# yard-ice-toplevel.net
KiCad netlist of a schematic drawn in Altium Designer
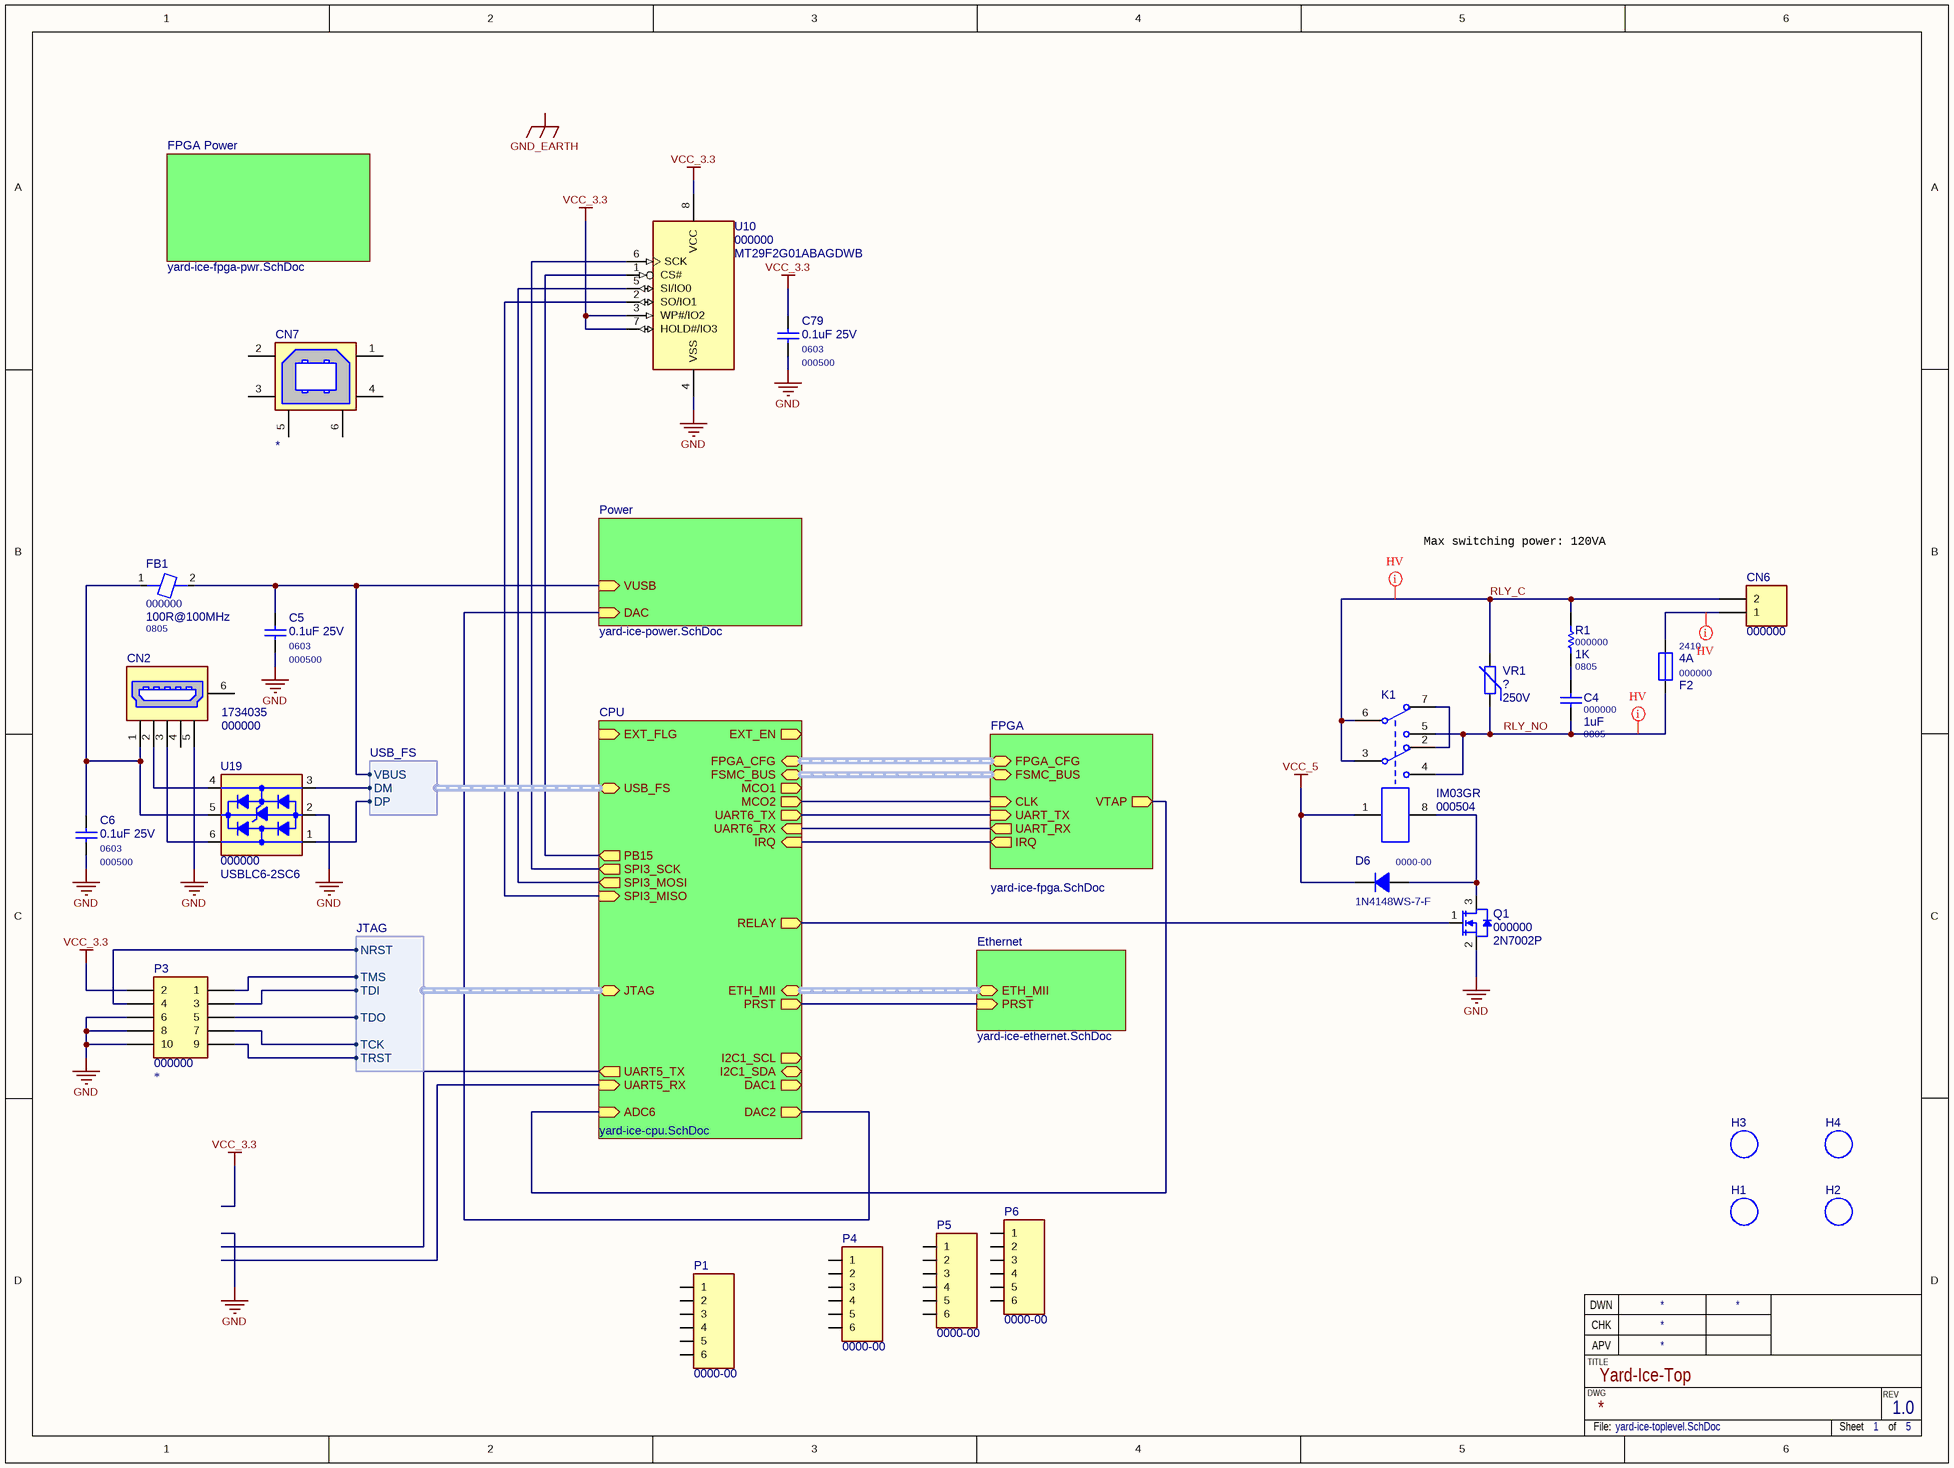
[diagram p0: yard-ice-toplevel.SchDoc]

(export (version "E")
  (design (tool "Eeschema 10.0.6"))
  (components
    (comp (ref "C4")
      (value "000000")
      (footprint "C0805HV")
      (description "SMD Ceramic Chip Capacitor - 0805")
      (fields (field (name "ALTIUM_VALUE") "1uF") (field (name "PACKAGE") "0805"))
      (libsource (lib "discrete-sm") (part "C0805"))
    )
    (comp (ref "C5")
      (value "000500")
      (footprint "C0603M")
      (description "SMD Ceramic Chip Capacitor - 0603 - X7R")
      (fields
        (field (name "ALTIUM_VALUE") "0.1uF 25V")
        (field (name "PACKAGE") "0603")
        (field (name "MF") "TDK")
      )
      (libsource (lib "discrete-sm") (part "C0603"))
    )
    (comp (ref "C6")
      (value "000500")
      (footprint "C0603M")
      (description "SMD Ceramic Chip Capacitor - 0603 - X7R")
      (fields
        (field (name "ALTIUM_VALUE") "0.1uF 25V")
        (field (name "PACKAGE") "0603")
        (field (name "MF") "TDK")
      )
      (libsource (lib "discrete-sm") (part "C0603"))
    )
    (comp (ref "C79")
      (value "000500")
      (footprint "C0603M")
      (description "SMD Ceramic Chip Capacitor - 0603 - X7R")
      (fields
        (field (name "ALTIUM_VALUE") "0.1uF 25V")
        (field (name "PACKAGE") "0603")
        (field (name "MF") "TDK")
      )
      (libsource (lib "discrete-sm") (part "C0603"))
    )
    (comp (ref "CN2")
      (value "1734035")
      (footprint "1734035")
      (description "USB Type B Mini - Right Angle - SMD")
      (fields (field (name "MF") "Tyco") (field (name "PN") "000000") (field (name "Comment") "000000"))
      (libsource (lib "tyco-conn") (part "1734035"))
    )
    (comp (ref "CN6")
      (value "000000")
      (footprint "691322110002")
      (description "Terminal Block, Header, 2-Pos")
      (libsource (lib "wurth") (part "Term Blk 2"))
    )
    (comp (ref "CN7")
      (value "*")
      (footprint "4-1734376")
      (description "USB Type B - Right Angle - Thru Hole")
      (libsource (lib "tyco-conn") (part "4-1734376"))
    )
    (comp (ref "D6")
      (value "0000-00")
      (footprint "SOD-323-M")
      (description "Fast Switching Diode 100V 150mA")
      (fields (field (name "MF") "Diodes Inc") (field (name "MF PN") "1N4148WS-7-F"))
      (libsource (lib "diodes-inc") (part "1N4148WS"))
    )
    (comp (ref "F2")
      (value "000000")
      (footprint "F2410")
      (fields (field (name "PACKAGE") "2410") (field (name "ALTIUM_VALUE") "4A"))
      (libsource (lib "discrete-sm") (part "F2410"))
    )
    (comp (ref "FB1")
      (value "000000")
      (footprint "L0805M")
      (description "SMD Chip Ferrite Bead - 0805")
      (fields (field (name "ALTIUM_VALUE") "100R@100MHz") (field (name "PACKAGE") "0805"))
      (libsource (lib "discrete-sm") (part "FB0805"))
    )
    (comp (ref "H1")
      (value "Hole Non Plated")
      (footprint "Hole NP 3.2x5.0x5.0")
      (libsource (lib "mechanical") (part "Hole Non Plated"))
    )
    (comp (ref "H2")
      (value "Hole Non Plated")
      (footprint "Hole NP 3.2x5.0x5.0")
      (libsource (lib "mechanical") (part "Hole Non Plated"))
    )
    (comp (ref "H3")
      (value "Hole Non Plated")
      (footprint "Hole NP 3.2x5.0x5.0")
      (libsource (lib "mechanical") (part "Hole Non Plated"))
    )
    (comp (ref "H4")
      (value "Hole Non Plated")
      (footprint "Hole NP 3.2x5.0x5.0")
      (libsource (lib "mechanical") (part "Hole Non Plated"))
    )
    (comp (ref "K1")
      (value "000504")
      (footprint "Relay-10X6")
      (description "Dual-Pole Dual-Throw Relay")
      (fields (field (name "ALTIUM_VALUE") "IM03GR") (field (name "MF") "Tyco"))
      (libsource (lib "sm-electromechanical") (part "Relay-DPDT"))
    )
    (comp (ref "P1")
      (value "0000-00")
      (footprint "SsW-106-01-G-S")
      (description "Header, 6-Pin")
      (fields (field (name "MF") "Samtec"))
      (libsource (lib "samtec-board-to-board") (part "Header 6"))
    )
    (comp (ref "P3")
      (value "000000")
      (footprint "TSW-105-07-G-D")
      (description "Socket 5-Pin, Dual row")
      (fields (field (name "ALTIUM_VALUE") "*"))
      (libsource (lib "samtec-std-hdr") (part "Header 5X2"))
    )
    (comp (ref "P4")
      (value "0000-00")
      (footprint "SsW-106-01-G-S")
      (description "Header, 6-Pin")
      (fields (field (name "MF") "Samtec"))
      (libsource (lib "samtec-board-to-board") (part "Header 6"))
    )
    (comp (ref "P5")
      (value "0000-00")
      (footprint "SsW-106-01-G-S")
      (description "Header, 6-Pin")
      (fields (field (name "MF") "Samtec"))
      (libsource (lib "samtec-board-to-board") (part "Header 6"))
    )
    (comp (ref "P6")
      (value "0000-00")
      (footprint "SsW-106-01-G-S")
      (description "Header, 6-Pin")
      (fields (field (name "MF") "Samtec"))
      (libsource (lib "samtec-board-to-board") (part "Header 6"))
    )
    (comp (ref "Q1")
      (value "000000")
      (footprint "SOT-23-M")
      (description "N-Channel MOSFET 60V 360mA SOT-23")
      (fields (field (name "ALTIUM_VALUE") "2N7002P"))
      (libsource (lib "nxp") (part "2N7002P"))
    )
    (comp (ref "R1")
      (value "000000")
      (footprint "R0805HV")
      (description "SMD Chip Resistor - 0805")
      (fields (field (name "ALTIUM_VALUE") "1K") (field (name "PACKAGE") "0805"))
      (libsource (lib "discrete-sm") (part "R0805"))
    )
    (comp (ref "U10")
      (value "000000")
      (footprint "U-PDFN-8")
      (description "2Gb NANDl Flash Memory,  133MHz, SPI")
      (fields (field (name "MF") "Micron") (field (name "ALTIUM_VALUE") "MT29F2G01ABAGDWB"))
      (libsource (lib "micron") (part "MT29F2G01ABAGDWB"))
    )
    (comp (ref "U19")
      (value "000000")
      (footprint "SOT23-6L")
      (description "USB ESD Protection")
      (fields (field (name "MF") "STMicroelectronics") (field (name "ALTIUM_VALUE") "USBLC6-2SC6"))
      (libsource (lib "st") (part "USBLC6-2SC6"))
    )
    (comp (ref "VR1")
      (value "?")
      (footprint "MOV7x4.8-5.0")
      (description "Varistor (Voltage-Sensitive Resistor)")
      (fields (field (name "ALTIUM_VALUE") "250V"))
      (libsource (lib "discrete-pth") (part "Varistor"))
    )
  )
  (nets
    (net (code "15") (name "/PB15") (class "Default")
      (node (ref "U10") (pin "1") (pinfunction "CS#_1") (pintype "input"))
    )
    (net (code "17") (name "/RELAY") (class "Default")
      (node (ref "Q1") (pin "1") (pinfunction "G_1") (pintype "passive"))
    )
    (net (code "18") (name "/RLY_C") (class "Default")
      (node (ref "CN6") (pin "2") (pinfunction "2_2") (pintype "passive"))
      (node (ref "K1") (pin "3") (pinfunction "3_3") (pintype "passive"))
      (node (ref "K1") (pin "6") (pinfunction "6_6") (pintype "passive"))
      (node (ref "R1") (pin "2") (pinfunction "2_2") (pintype "passive"))
      (node (ref "VR1") (pin "2") (pinfunction "2_2") (pintype "passive"))
    )
    (net (code "19") (name "/RLY_NO") (class "Default")
      (node (ref "C4") (pin "2") (pinfunction "2_2") (pintype "passive"))
      (node (ref "F2") (pin "1") (pinfunction "1_1") (pintype "passive"))
      (node (ref "K1") (pin "4") (pinfunction "4_4") (pintype "passive"))
      (node (ref "K1") (pin "5") (pinfunction "5_5") (pintype "passive"))
      (node (ref "VR1") (pin "1") (pinfunction "1_1") (pintype "passive"))
    )
    (net (code "20") (name "/SPI3_MISO") (class "Default")
      (node (ref "U10") (pin "2") (pinfunction "SO/IO1_2") (pintype "bidirectional"))
    )
    (net (code "21") (name "/SPI3_MOSI") (class "Default")
      (node (ref "U10") (pin "5") (pinfunction "SI/IO0_5") (pintype "bidirectional"))
    )
    (net (code "22") (name "/SPI3_SCK") (class "Default")
      (node (ref "U10") (pin "6") (pinfunction "SCK_6") (pintype "input"))
    )
    (net (code "28") (name "/VUSB") (class "Default")
      (node (ref "C5") (pin "1") (pinfunction "1_1") (pintype "passive"))
      (node (ref "FB1") (pin "2") (pinfunction "2_2") (pintype "passive"))
    )
    (net (code "31") (name "GND") (class "Default")
      (node (ref "C5") (pin "2") (pinfunction "2_2") (pintype "passive"))
      (node (ref "C6") (pin "2") (pinfunction "2_2") (pintype "passive"))
      (node (ref "C79") (pin "2") (pinfunction "2_2") (pintype "passive"))
      (node (ref "CN2") (pin "5") (pinfunction "SHIELD_5") (pintype "passive"))
      (node (ref "P3") (pin "10") (pinfunction "10_10") (pintype "passive"))
      (node (ref "P3") (pin "6") (pinfunction "6_6") (pintype "passive"))
      (node (ref "P3") (pin "8") (pinfunction "8_8") (pintype "passive"))
      (node (ref "Q1") (pin "2") (pinfunction "S_2") (pintype "passive"))
      (node (ref "U10") (pin "4") (pinfunction "VSS_4") (pintype "power_in"))
      (node (ref "U19") (pin "2") (pinfunction "GND_2") (pintype "power_in"))
    )
    (net (code "33") (name "Net-(C4-Pad1)") (class "Default")
      (node (ref "C4") (pin "1") (pinfunction "1_1") (pintype "passive"))
      (node (ref "R1") (pin "1") (pinfunction "1_1") (pintype "passive"))
    )
    (net (code "34") (name "Net-(CN6-Pad1)") (class "Default")
      (node (ref "CN6") (pin "1") (pinfunction "1_1") (pintype "passive"))
      (node (ref "F2") (pin "2") (pinfunction "2_2") (pintype "passive"))
    )
    (net (code "35") (name "Net-(D6-A)") (class "Default")
      (node (ref "D6") (pin "1") (pinfunction "A_1") (pintype "passive"))
      (node (ref "K1") (pin "8") (pinfunction "8_8") (pintype "passive"))
      (node (ref "Q1") (pin "3") (pinfunction "D_3") (pintype "passive"))
    )
    (net (code "36") (name "Net-(K1-Pad2)") (class "Default")
      (node (ref "K1") (pin "2") (pinfunction "2_2") (pintype "passive"))
      (node (ref "K1") (pin "7") (pinfunction "7_7") (pintype "passive"))
    )
    (net (code "37") (name "Net-(U19-I{slash}O1)") (class "Default")
      (node (ref "CN2") (pin "3") (pinfunction "3_3") (pintype "passive"))
      (node (ref "U19") (pin "6") (pinfunction "I/O1_6") (pintype "open_collector"))
    )
    (net (code "38") (name "Net-(U19-I{slash}O2)") (class "Default")
      (node (ref "CN2") (pin "2") (pinfunction "2_2") (pintype "passive"))
      (node (ref "U19") (pin "4") (pinfunction "I/O2_4") (pintype "open_collector"))
    )
    (net (code "39") (name "Net-(U19-VBUS)") (class "Default")
      (node (ref "C6") (pin "1") (pinfunction "1_1") (pintype "passive"))
      (node (ref "CN2") (pin "1") (pinfunction "1_1") (pintype "passive"))
      (node (ref "FB1") (pin "1") (pinfunction "1_1") (pintype "passive"))
      (node (ref "U19") (pin "5") (pinfunction "VBUS_5") (pintype "power_in"))
    )
    (net (code "40") (name "VCC_3.3") (class "Default")
      (node (ref "C79") (pin "1") (pinfunction "1_1") (pintype "passive"))
      (node (ref "P3") (pin "2") (pinfunction "2_2") (pintype "passive"))
      (node (ref "U10") (pin "3") (pinfunction "WP#/IO2_3") (pintype "input"))
      (node (ref "U10") (pin "7") (pinfunction "HOLD#/IO3_7") (pintype "bidirectional"))
      (node (ref "U10") (pin "8") (pinfunction "VCC_8") (pintype "power_in"))
    )
    (net (code "41") (name "VCC_5") (class "Default")
      (node (ref "D6") (pin "2") (pinfunction "K_2") (pintype "passive"))
      (node (ref "K1") (pin "1") (pinfunction "1_1") (pintype "passive"))
    )
    (net (code "42") (name "unconnected-(CN2-Pad4)") (class "Default")
      (node (ref "CN2") (pin "4") (pinfunction "4_4") (pintype "passive"))
    )
    (net (code "43") (name "unconnected-(CN2-SHIELD-Pad6)") (class "Default")
      (node (ref "CN2") (pin "6") (pinfunction "SHIELD_6") (pintype "passive"))
    )
    (net (code "44") (name "unconnected-(CN7-Pad1)") (class "Default")
      (node (ref "CN7") (pin "1") (pinfunction "1_1") (pintype "passive"))
    )
    (net (code "45") (name "unconnected-(CN7-Pad2)") (class "Default")
      (node (ref "CN7") (pin "2") (pinfunction "2_2") (pintype "passive"))
    )
    (net (code "46") (name "unconnected-(CN7-Pad3)") (class "Default")
      (node (ref "CN7") (pin "3") (pinfunction "3_3") (pintype "passive"))
    )
    (net (code "47") (name "unconnected-(CN7-Pad4)") (class "Default")
      (node (ref "CN7") (pin "4") (pinfunction "4_4") (pintype "passive"))
    )
    (net (code "48") (name "unconnected-(CN7-SHIELD-Pad5)") (class "Default")
      (node (ref "CN7") (pin "5") (pinfunction "SHIELD_5") (pintype "passive"))
    )
    (net (code "49") (name "unconnected-(CN7-SHIELD-Pad6)") (class "Default")
      (node (ref "CN7") (pin "6") (pinfunction "SHIELD_6") (pintype "passive"))
    )
    (net (code "50") (name "unconnected-(P1-Pad1)") (class "Default")
      (node (ref "P1") (pin "1") (pinfunction "1_1") (pintype "passive"))
    )
    (net (code "51") (name "unconnected-(P1-Pad2)") (class "Default")
      (node (ref "P1") (pin "2") (pinfunction "2_2") (pintype "passive"))
    )
    (net (code "52") (name "unconnected-(P1-Pad3)") (class "Default")
      (node (ref "P1") (pin "3") (pinfunction "3_3") (pintype "passive"))
    )
    (net (code "53") (name "unconnected-(P1-Pad4)") (class "Default")
      (node (ref "P1") (pin "4") (pinfunction "4_4") (pintype "passive"))
    )
    (net (code "54") (name "unconnected-(P1-Pad5)") (class "Default")
      (node (ref "P1") (pin "5") (pinfunction "5_5") (pintype "passive"))
    )
    (net (code "55") (name "unconnected-(P1-Pad6)") (class "Default")
      (node (ref "P1") (pin "6") (pinfunction "6_6") (pintype "passive"))
    )
    (net (code "56") (name "unconnected-(P3-Pad1)") (class "Default")
      (node (ref "P3") (pin "1") (pinfunction "1_1") (pintype "passive"))
    )
    (net (code "57") (name "unconnected-(P3-Pad3)") (class "Default")
      (node (ref "P3") (pin "3") (pinfunction "3_3") (pintype "passive"))
    )
    (net (code "58") (name "unconnected-(P3-Pad4)") (class "Default")
      (node (ref "P3") (pin "4") (pinfunction "4_4") (pintype "passive"))
    )
    (net (code "59") (name "unconnected-(P3-Pad5)") (class "Default")
      (node (ref "P3") (pin "5") (pinfunction "5_5") (pintype "passive"))
    )
    (net (code "60") (name "unconnected-(P3-Pad7)") (class "Default")
      (node (ref "P3") (pin "7") (pinfunction "7_7") (pintype "passive"))
    )
    (net (code "61") (name "unconnected-(P3-Pad9)") (class "Default")
      (node (ref "P3") (pin "9") (pinfunction "9_9") (pintype "passive"))
    )
    (net (code "62") (name "unconnected-(P4-Pad1)") (class "Default")
      (node (ref "P4") (pin "1") (pinfunction "1_1") (pintype "passive"))
    )
    (net (code "63") (name "unconnected-(P4-Pad2)") (class "Default")
      (node (ref "P4") (pin "2") (pinfunction "2_2") (pintype "passive"))
    )
    (net (code "64") (name "unconnected-(P4-Pad3)") (class "Default")
      (node (ref "P4") (pin "3") (pinfunction "3_3") (pintype "passive"))
    )
    (net (code "65") (name "unconnected-(P4-Pad4)") (class "Default")
      (node (ref "P4") (pin "4") (pinfunction "4_4") (pintype "passive"))
    )
    (net (code "66") (name "unconnected-(P4-Pad5)") (class "Default")
      (node (ref "P4") (pin "5") (pinfunction "5_5") (pintype "passive"))
    )
    (net (code "67") (name "unconnected-(P4-Pad6)") (class "Default")
      (node (ref "P4") (pin "6") (pinfunction "6_6") (pintype "passive"))
    )
    (net (code "68") (name "unconnected-(P5-Pad1)") (class "Default")
      (node (ref "P5") (pin "1") (pinfunction "1_1") (pintype "passive"))
    )
    (net (code "69") (name "unconnected-(P5-Pad2)") (class "Default")
      (node (ref "P5") (pin "2") (pinfunction "2_2") (pintype "passive"))
    )
    (net (code "70") (name "unconnected-(P5-Pad3)") (class "Default")
      (node (ref "P5") (pin "3") (pinfunction "3_3") (pintype "passive"))
    )
    (net (code "71") (name "unconnected-(P5-Pad4)") (class "Default")
      (node (ref "P5") (pin "4") (pinfunction "4_4") (pintype "passive"))
    )
    (net (code "72") (name "unconnected-(P5-Pad5)") (class "Default")
      (node (ref "P5") (pin "5") (pinfunction "5_5") (pintype "passive"))
    )
    (net (code "73") (name "unconnected-(P5-Pad6)") (class "Default")
      (node (ref "P5") (pin "6") (pinfunction "6_6") (pintype "passive"))
    )
    (net (code "74") (name "unconnected-(P6-Pad1)") (class "Default")
      (node (ref "P6") (pin "1") (pinfunction "1_1") (pintype "passive"))
    )
    (net (code "75") (name "unconnected-(P6-Pad2)") (class "Default")
      (node (ref "P6") (pin "2") (pinfunction "2_2") (pintype "passive"))
    )
    (net (code "76") (name "unconnected-(P6-Pad3)") (class "Default")
      (node (ref "P6") (pin "3") (pinfunction "3_3") (pintype "passive"))
    )
    (net (code "77") (name "unconnected-(P6-Pad4)") (class "Default")
      (node (ref "P6") (pin "4") (pinfunction "4_4") (pintype "passive"))
    )
    (net (code "78") (name "unconnected-(P6-Pad5)") (class "Default")
      (node (ref "P6") (pin "5") (pinfunction "5_5") (pintype "passive"))
    )
    (net (code "79") (name "unconnected-(P6-Pad6)") (class "Default")
      (node (ref "P6") (pin "6") (pinfunction "6_6") (pintype "passive"))
    )
    (net (code "80") (name "unconnected-(U19-IO{slash}1-Pad1)") (class "Default")
      (node (ref "U19") (pin "1") (pinfunction "IO/1_1") (pintype "power_in"))
    )
    (net (code "81") (name "unconnected-(U19-IO{slash}2-Pad3)") (class "Default")
      (node (ref "U19") (pin "3") (pinfunction "IO/2_3") (pintype "power_in"))
    )
  )
)
